# tweeq-eMod_LEDPB.net
KiCad netlist of a schematic drawn in EAGLE
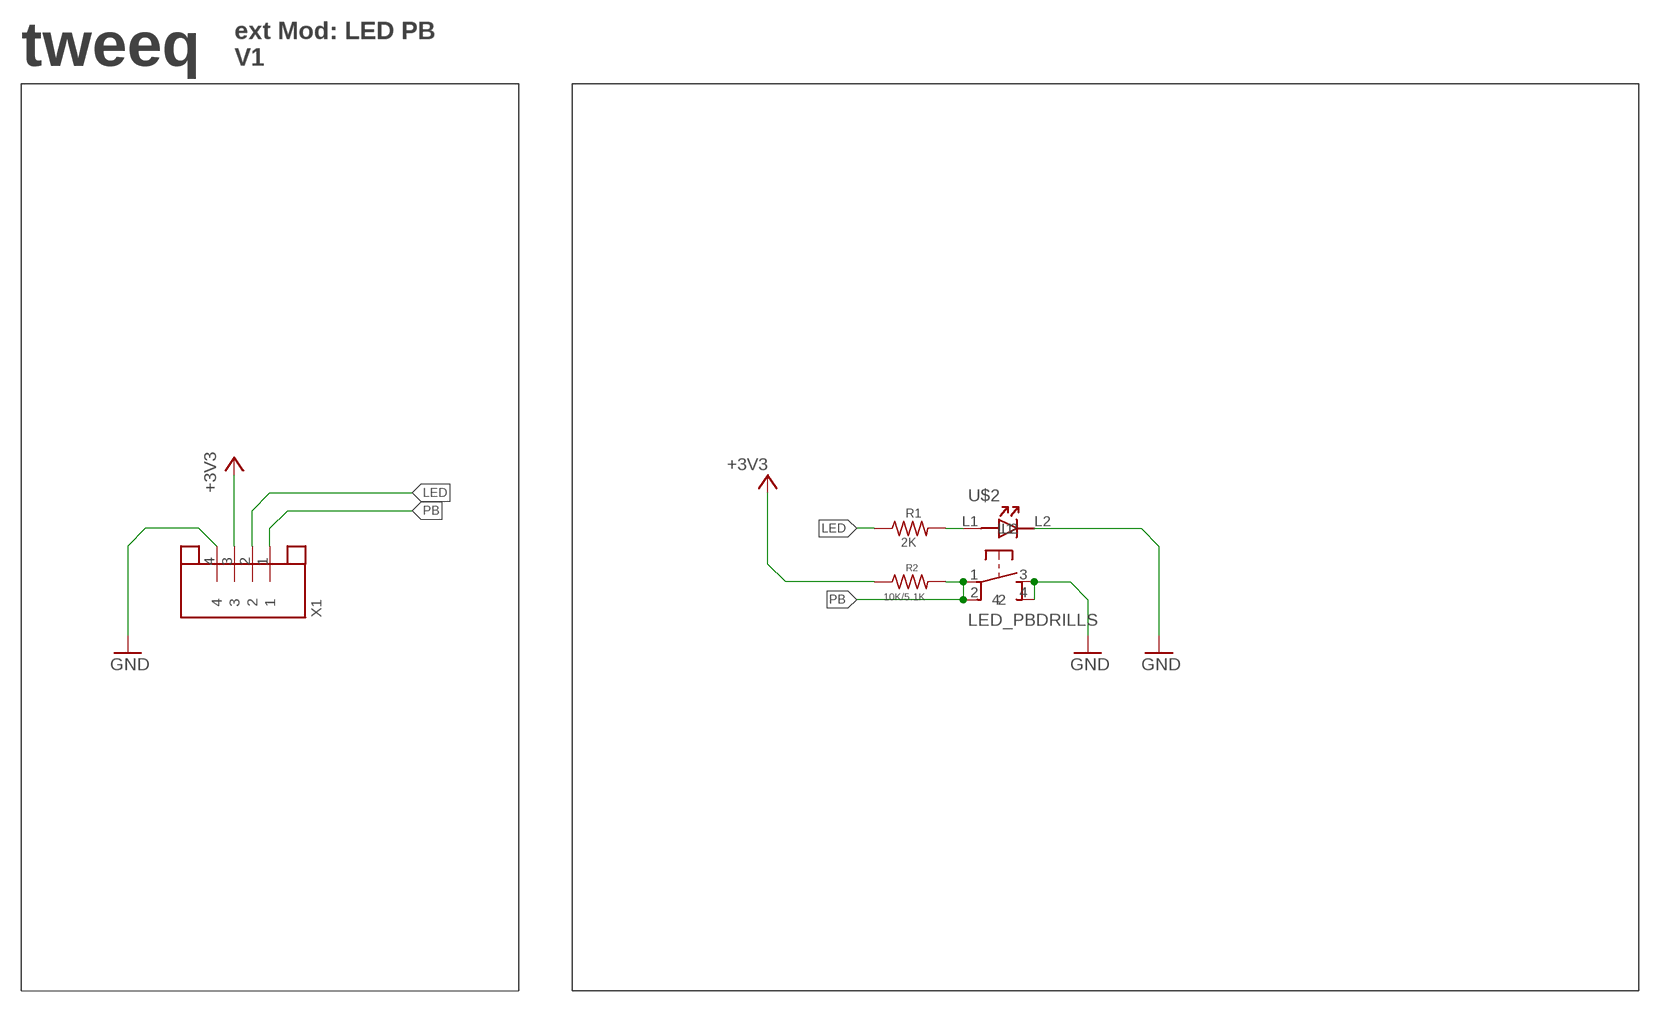
[diagram p0: schematic, sheet 1]

(export (version "E")
  (design (tool "Eeschema 10.0.6"))
  (components
    (comp (ref "R1")
      (value "2K")
      (footprint "eagle-import:R0603")
      (libsource (lib "eagle-import") (part "R-US_R0603"))
    )
    (comp (ref "R2")
      (value "10K/5.1K")
      (footprint "eagle-import:R0603")
      (libsource (lib "eagle-import") (part "R-US_R0603"))
    )
    (comp (ref "U$2")
      (value "LED_PBDRILLS")
      (footprint "eagle-import:LED_PB_12X12_SMD_HOLES")
      (libsource (lib "eagle-import") (part "LED_PBDRILLS"))
    )
    (comp (ref "X1")
      (value "JST-4PINSH")
      (footprint "eagle-import:SH1.0-4PIN")
      (libsource (lib "eagle-import") (part "JST-4PINSH"))
    )
  )
  (nets
    (net (code "1") (name "+3V3") (class "Default")
      (node (ref "R2") (pin "1") (pinfunction "1_1") (pintype "passive"))
      (node (ref "X1") (pin "3") (pinfunction "3_3") (pintype "bidirectional"))
    )
    (net (code "2") (name "GND") (class "Default")
      (node (ref "U$2") (pin "3") (pinfunction "3_3") (pintype "passive"))
      (node (ref "U$2") (pin "4") (pinfunction "4_4") (pintype "passive"))
      (node (ref "U$2") (pin "L2") (pinfunction "L2_L2") (pintype "bidirectional"))
      (node (ref "X1") (pin "4") (pinfunction "4_4") (pintype "bidirectional"))
    )
    (net (code "3") (name "LED") (class "Default")
      (node (ref "R1") (pin "1") (pinfunction "1_1") (pintype "passive"))
      (node (ref "X1") (pin "2") (pinfunction "2_2") (pintype "bidirectional"))
    )
    (net (code "4") (name "Net-(R1-Pad2)") (class "Default")
      (node (ref "R1") (pin "2") (pinfunction "2_2") (pintype "passive"))
      (node (ref "U$2") (pin "L1") (pinfunction "L1_L1") (pintype "bidirectional"))
    )
    (net (code "5") (name "PB") (class "Default")
      (node (ref "R2") (pin "2") (pinfunction "2_2") (pintype "passive"))
      (node (ref "U$2") (pin "1") (pinfunction "1_1") (pintype "passive"))
      (node (ref "U$2") (pin "2") (pinfunction "2_2") (pintype "passive"))
      (node (ref "X1") (pin "1") (pinfunction "1_1") (pintype "bidirectional"))
    )
  )
)
